# main1.net
KiCad netlist of a schematic drawn in EAGLE
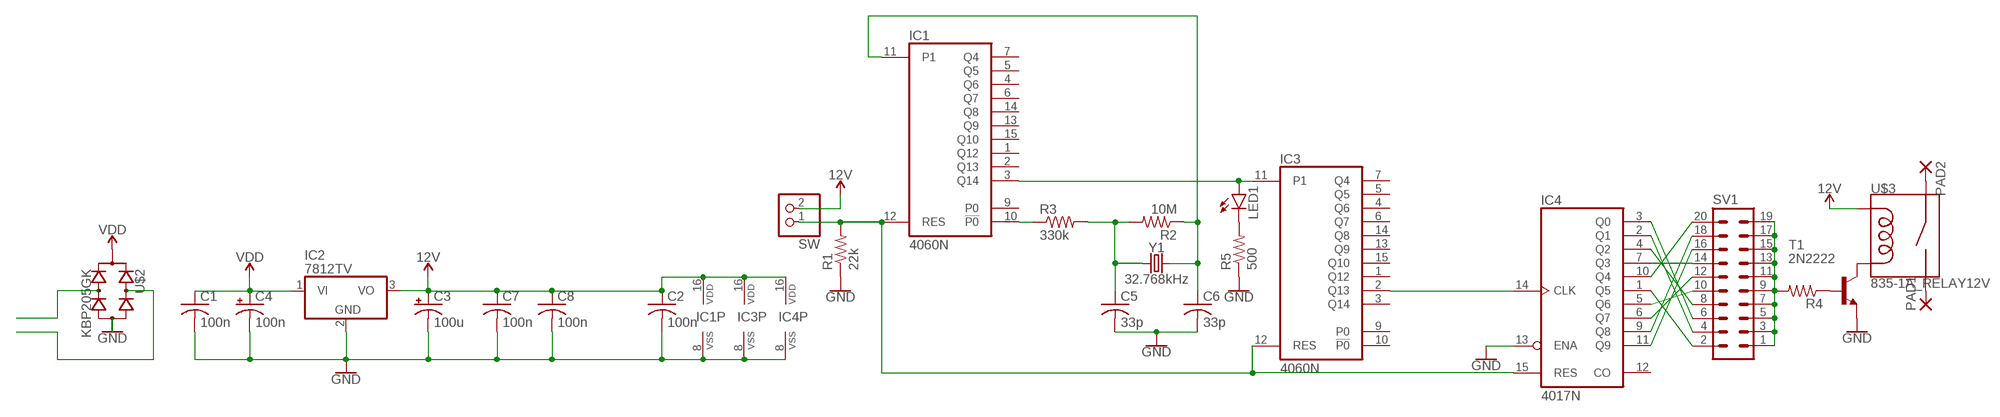
[diagram p0: schematic, sheet 1]

(export (version "E")
  (design (tool "Eeschema 10.0.6"))
  (components
    (comp (ref "C1")
      (value "100n")
      (footprint "eagle-import:C025-025X050")
      (libsource (lib "eagle-import") (part "C-US025-025X050"))
    )
    (comp (ref "C2")
      (value "100n")
      (footprint "eagle-import:C025-025X050")
      (libsource (lib "eagle-import") (part "C-US025-025X050"))
    )
    (comp (ref "C3")
      (value "100u")
      (footprint "eagle-import:E2-5")
      (libsource (lib "eagle-import") (part "CPOL-USE2-5"))
    )
    (comp (ref "C4")
      (value "100n")
      (footprint "eagle-import:E2-5")
      (libsource (lib "eagle-import") (part "CPOL-USE2-5"))
    )
    (comp (ref "C5")
      (value "33p")
      (footprint "eagle-import:C025-025X050")
      (libsource (lib "eagle-import") (part "C-US025-025X050"))
    )
    (comp (ref "C6")
      (value "33p")
      (footprint "eagle-import:C025-025X050")
      (libsource (lib "eagle-import") (part "C-US025-025X050"))
    )
    (comp (ref "C7")
      (value "100n")
      (footprint "eagle-import:C025-025X050")
      (libsource (lib "eagle-import") (part "C-US025-025X050"))
    )
    (comp (ref "C8")
      (value "100n")
      (footprint "eagle-import:C025-025X050")
      (libsource (lib "eagle-import") (part "C-US025-025X050"))
    )
    (comp (ref "IC1")
      (value "4060N")
      (footprint "eagle-import:DIL16")
      (libsource (lib "eagle-import") (part "4060N"))
    )
    (comp (ref "IC2")
      (value "7812TV")
      (footprint "eagle-import:TO220V")
      (libsource (lib "eagle-import") (part "78TV12"))
    )
    (comp (ref "IC3")
      (value "4060N")
      (footprint "eagle-import:DIL16")
      (libsource (lib "eagle-import") (part "4060N"))
    )
    (comp (ref "IC4")
      (value "4017N")
      (footprint "eagle-import:DIL16")
      (libsource (lib "eagle-import") (part "4017N"))
    )
    (comp (ref "LED1")
      (value "LED3MM")
      (footprint "eagle-import:LED3MM")
      (libsource (lib "eagle-import") (part "LED3MM"))
    )
    (comp (ref "PAD1")
      (value "2,54/1,0")
      (footprint "eagle-import:2,54_1,0")
      (libsource (lib "eagle-import") (part "2,54/1,0"))
    )
    (comp (ref "PAD2")
      (value "2,54/1,0")
      (footprint "eagle-import:2,54_1,0")
      (libsource (lib "eagle-import") (part "2,54/1,0"))
    )
    (comp (ref "R1")
      (value "22k")
      (footprint "eagle-import:0207_7")
      (libsource (lib "eagle-import") (part "R-US_0207/7"))
    )
    (comp (ref "R2")
      (value "10M")
      (footprint "eagle-import:0207_7")
      (libsource (lib "eagle-import") (part "R-US_0207/7"))
    )
    (comp (ref "R3")
      (value "330k")
      (footprint "eagle-import:0207_7")
      (libsource (lib "eagle-import") (part "R-US_0207/7"))
    )
    (comp (ref "R4")
      (value "R-US_0207/2V")
      (footprint "eagle-import:0207_2V")
      (libsource (lib "eagle-import") (part "R-US_0207/2V"))
    )
    (comp (ref "R5")
      (value "500")
      (footprint "eagle-import:0207_7")
      (libsource (lib "eagle-import") (part "R-US_0207/7"))
    )
    (comp (ref "SV1")
      (value "MA10-2")
      (footprint "eagle-import:MA10-2")
      (libsource (lib "eagle-import") (part "MA10-2"))
    )
    (comp (ref "SW")
      (value "PINHD-1X2")
      (footprint "eagle-import:1X02")
      (libsource (lib "eagle-import") (part "PINHD-1X2"))
    )
    (comp (ref "T1")
      (value "2N2222")
      (footprint "eagle-import:TO92-EBC-OVAL")
      (libsource (lib "eagle-import") (part "2N2222"))
    )
    (comp (ref "U$2")
      (value "KBP205GK")
      (footprint "eagle-import:KBP205G")
      (libsource (lib "eagle-import") (part "KBP205GK"))
    )
    (comp (ref "U$3")
      (value "835-1A_RELAY12V")
      (footprint "eagle-import:835-1A_RELAY_12V")
      (libsource (lib "eagle-import") (part "835-1A_RELAY12V"))
    )
    (comp (ref "Y1")
      (value "32.768kHz")
      (footprint "eagle-import:CRYSTAL-PTH-2X6-CYL")
      (libsource (lib "eagle-import") (part "CRYSTAL-32.768KHZPTH-2X6"))
    )
  )
  (nets
    (net (code "1") (name "12V") (class "Default")
      (node (ref "C2") (pin "1") (pinfunction "1_1") (pintype "passive"))
      (node (ref "C3") (pin "+") (pinfunction "+_+") (pintype "passive"))
      (node (ref "C7") (pin "1") (pinfunction "1_1") (pintype "passive"))
      (node (ref "C8") (pin "1") (pinfunction "1_1") (pintype "passive"))
      (node (ref "IC1") (pin "16") (pinfunction "VDD_16") (pintype "power_in"))
      (node (ref "IC2") (pin "3") (pinfunction "VO_3") (pintype "passive"))
      (node (ref "IC3") (pin "16") (pinfunction "VDD_16") (pintype "power_in"))
      (node (ref "IC4") (pin "16") (pinfunction "VDD_16") (pintype "power_in"))
      (node (ref "SW") (pin "2") (pinfunction "2_2") (pintype "passive"))
      (node (ref "U$3") (pin "P$1") (pinfunction "COIL1_P$1") (pintype "bidirectional"))
    )
    (net (code "2") (name "GND") (class "Default")
      (node (ref "C1") (pin "2") (pinfunction "2_2") (pintype "passive"))
      (node (ref "C2") (pin "2") (pinfunction "2_2") (pintype "passive"))
      (node (ref "C3") (pin "-") (pinfunction "-_-") (pintype "passive"))
      (node (ref "C4") (pin "-") (pinfunction "-_-") (pintype "passive"))
      (node (ref "C5") (pin "2") (pinfunction "2_2") (pintype "passive"))
      (node (ref "C6") (pin "2") (pinfunction "2_2") (pintype "passive"))
      (node (ref "C7") (pin "2") (pinfunction "2_2") (pintype "passive"))
      (node (ref "C8") (pin "2") (pinfunction "2_2") (pintype "passive"))
      (node (ref "IC1") (pin "8") (pinfunction "VSS_8") (pintype "power_in"))
      (node (ref "IC2") (pin "2") (pinfunction "GND_2") (pintype "passive"))
      (node (ref "IC3") (pin "8") (pinfunction "VSS_8") (pintype "power_in"))
      (node (ref "IC4") (pin "13") (pinfunction "ENA_13") (pintype "input"))
      (node (ref "IC4") (pin "8") (pinfunction "VSS_8") (pintype "power_in"))
      (node (ref "R1") (pin "1") (pinfunction "1_1") (pintype "passive"))
      (node (ref "R5") (pin "1") (pinfunction "1_1") (pintype "passive"))
      (node (ref "T1") (pin "E") (pinfunction "E_E") (pintype "passive"))
      (node (ref "U$2") (pin "-") (pinfunction "-_-") (pintype "passive"))
    )
    (net (code "3") (name "Net-(C5-Pad1)") (class "Default")
      (node (ref "C5") (pin "1") (pinfunction "1_1") (pintype "passive"))
      (node (ref "R2") (pin "2") (pinfunction "2_2") (pintype "passive"))
      (node (ref "R3") (pin "2") (pinfunction "2_2") (pintype "passive"))
      (node (ref "Y1") (pin "1") (pinfunction "1_1") (pintype "passive"))
    )
    (net (code "4") (name "Net-(IC1A-P1)") (class "Default")
      (node (ref "C6") (pin "1") (pinfunction "1_1") (pintype "passive"))
      (node (ref "IC1") (pin "11") (pinfunction "P1_11") (pintype "input"))
      (node (ref "R2") (pin "1") (pinfunction "1_1") (pintype "passive"))
      (node (ref "Y1") (pin "2") (pinfunction "2_2") (pintype "passive"))
    )
    (net (code "5") (name "Net-(IC1A-Q14)") (class "Default")
      (node (ref "IC1") (pin "3") (pinfunction "Q14_3") (pintype "output"))
      (node (ref "IC3") (pin "11") (pinfunction "P1_11") (pintype "input"))
      (node (ref "LED1") (pin "A") (pinfunction "A_A") (pintype "passive"))
    )
    (net (code "6") (name "Net-(IC1A-RES)") (class "Default")
      (node (ref "IC1") (pin "12") (pinfunction "RES_12") (pintype "input"))
      (node (ref "IC3") (pin "12") (pinfunction "RES_12") (pintype "input"))
      (node (ref "IC4") (pin "15") (pinfunction "RES_15") (pintype "input"))
      (node (ref "R1") (pin "2") (pinfunction "2_2") (pintype "passive"))
      (node (ref "SW") (pin "1") (pinfunction "1_1") (pintype "passive"))
    )
    (net (code "7") (name "Net-(IC1A-~{P0})") (class "Default")
      (node (ref "IC1") (pin "10") (pinfunction "~{P0}_10") (pintype "output"))
      (node (ref "R3") (pin "1") (pinfunction "1_1") (pintype "passive"))
    )
    (net (code "8") (name "Net-(IC3A-Q13)") (class "Default")
      (node (ref "IC3") (pin "2") (pinfunction "Q13_2") (pintype "output"))
      (node (ref "IC4") (pin "14") (pinfunction "CLK_14") (pintype "input"))
    )
    (net (code "9") (name "Net-(IC4A-Q0)") (class "Default")
      (node (ref "IC4") (pin "3") (pinfunction "Q0_3") (pintype "output"))
      (node (ref "SV1") (pin "6") (pinfunction "6_6") (pintype "passive"))
    )
    (net (code "10") (name "Net-(IC4A-Q1)") (class "Default")
      (node (ref "IC4") (pin "2") (pinfunction "Q1_2") (pintype "output"))
      (node (ref "SV1") (pin "4") (pinfunction "4_4") (pintype "passive"))
    )
    (net (code "11") (name "Net-(IC4A-Q2)") (class "Default")
      (node (ref "IC4") (pin "4") (pinfunction "Q2_4") (pintype "output"))
      (node (ref "SV1") (pin "8") (pinfunction "8_8") (pintype "passive"))
    )
    (net (code "12") (name "Net-(IC4A-Q3)") (class "Default")
      (node (ref "IC4") (pin "7") (pinfunction "Q3_7") (pintype "output"))
      (node (ref "SV1") (pin "14") (pinfunction "14_14") (pintype "passive"))
    )
    (net (code "13") (name "Net-(IC4A-Q4)") (class "Default")
      (node (ref "IC4") (pin "10") (pinfunction "Q4_10") (pintype "output"))
      (node (ref "SV1") (pin "20") (pinfunction "20_20") (pintype "passive"))
    )
    (net (code "14") (name "Net-(IC4A-Q5)") (class "Default")
      (node (ref "IC4") (pin "1") (pinfunction "Q5_1") (pintype "output"))
      (node (ref "SV1") (pin "2") (pinfunction "2_2") (pintype "passive"))
    )
    (net (code "15") (name "Net-(IC4A-Q6)") (class "Default")
      (node (ref "IC4") (pin "5") (pinfunction "Q6_5") (pintype "output"))
      (node (ref "SV1") (pin "10") (pinfunction "10_10") (pintype "passive"))
    )
    (net (code "16") (name "Net-(IC4A-Q7)") (class "Default")
      (node (ref "IC4") (pin "6") (pinfunction "Q7_6") (pintype "output"))
      (node (ref "SV1") (pin "12") (pinfunction "12_12") (pintype "passive"))
    )
    (net (code "17") (name "Net-(IC4A-Q8)") (class "Default")
      (node (ref "IC4") (pin "9") (pinfunction "Q8_9") (pintype "output"))
      (node (ref "SV1") (pin "18") (pinfunction "18_18") (pintype "passive"))
    )
    (net (code "18") (name "Net-(IC4A-Q9)") (class "Default")
      (node (ref "IC4") (pin "11") (pinfunction "Q9_11") (pintype "output"))
      (node (ref "SV1") (pin "16") (pinfunction "16_16") (pintype "passive"))
    )
    (net (code "19") (name "Net-(LED1-C)") (class "Default")
      (node (ref "LED1") (pin "K") (pinfunction "C_K") (pintype "passive"))
      (node (ref "R5") (pin "2") (pinfunction "2_2") (pintype "passive"))
    )
    (net (code "20") (name "Net-(PAD1-P)") (class "Default")
      (node (ref "PAD1") (pin "1") (pinfunction "P_1") (pintype "passive"))
      (node (ref "U$3") (pin "P$4") (pinfunction "NO_P$4") (pintype "bidirectional"))
    )
    (net (code "21") (name "Net-(PAD2-P)") (class "Default")
      (node (ref "PAD2") (pin "1") (pinfunction "P_1") (pintype "passive"))
      (node (ref "U$3") (pin "P$3") (pinfunction "MAIN_P$3") (pintype "bidirectional"))
    )
    (net (code "22") (name "Net-(R4-Pad1)") (class "Default")
      (node (ref "R4") (pin "1") (pinfunction "1_1") (pintype "passive"))
      (node (ref "T1") (pin "B") (pinfunction "B_B") (pintype "passive"))
    )
    (net (code "23") (name "Net-(R4-Pad2)") (class "Default")
      (node (ref "R4") (pin "2") (pinfunction "2_2") (pintype "passive"))
      (node (ref "SV1") (pin "1") (pinfunction "1_1") (pintype "passive"))
      (node (ref "SV1") (pin "11") (pinfunction "11_11") (pintype "passive"))
      (node (ref "SV1") (pin "13") (pinfunction "13_13") (pintype "passive"))
      (node (ref "SV1") (pin "15") (pinfunction "15_15") (pintype "passive"))
      (node (ref "SV1") (pin "17") (pinfunction "17_17") (pintype "passive"))
      (node (ref "SV1") (pin "19") (pinfunction "19_19") (pintype "passive"))
      (node (ref "SV1") (pin "3") (pinfunction "3_3") (pintype "passive"))
      (node (ref "SV1") (pin "5") (pinfunction "5_5") (pintype "passive"))
      (node (ref "SV1") (pin "7") (pinfunction "7_7") (pintype "passive"))
      (node (ref "SV1") (pin "9") (pinfunction "9_9") (pintype "passive"))
    )
    (net (code "24") (name "Net-(U$3-COIL2)") (class "Default")
      (node (ref "T1") (pin "C") (pinfunction "C_C") (pintype "passive"))
      (node (ref "U$3") (pin "P$2") (pinfunction "COIL2_P$2") (pintype "bidirectional"))
    )
    (net (code "25") (name "VDD") (class "Default")
      (node (ref "C1") (pin "1") (pinfunction "1_1") (pintype "passive"))
      (node (ref "C4") (pin "+") (pinfunction "+_+") (pintype "passive"))
      (node (ref "IC2") (pin "1") (pinfunction "VI_1") (pintype "input"))
      (node (ref "U$2") (pin "+") (pinfunction "+_+") (pintype "passive"))
    )
    (net (code "26") (name "unconnected-(IC1A-P0-Pad9)") (class "Default")
      (node (ref "IC1") (pin "9") (pinfunction "P0_9") (pintype "output"))
    )
    (net (code "27") (name "unconnected-(IC1A-Q4-Pad7)") (class "Default")
      (node (ref "IC1") (pin "7") (pinfunction "Q4_7") (pintype "output"))
    )
    (net (code "28") (name "unconnected-(IC1A-Q5-Pad5)") (class "Default")
      (node (ref "IC1") (pin "5") (pinfunction "Q5_5") (pintype "output"))
    )
    (net (code "29") (name "unconnected-(IC1A-Q6-Pad4)") (class "Default")
      (node (ref "IC1") (pin "4") (pinfunction "Q6_4") (pintype "output"))
    )
    (net (code "30") (name "unconnected-(IC1A-Q7-Pad6)") (class "Default")
      (node (ref "IC1") (pin "6") (pinfunction "Q7_6") (pintype "output"))
    )
    (net (code "31") (name "unconnected-(IC1A-Q8-Pad14)") (class "Default")
      (node (ref "IC1") (pin "14") (pinfunction "Q8_14") (pintype "output"))
    )
    (net (code "32") (name "unconnected-(IC1A-Q9-Pad13)") (class "Default")
      (node (ref "IC1") (pin "13") (pinfunction "Q9_13") (pintype "output"))
    )
    (net (code "33") (name "unconnected-(IC1A-Q10-Pad15)") (class "Default")
      (node (ref "IC1") (pin "15") (pinfunction "Q10_15") (pintype "output"))
    )
    (net (code "34") (name "unconnected-(IC1A-Q12-Pad1)") (class "Default")
      (node (ref "IC1") (pin "1") (pinfunction "Q12_1") (pintype "output"))
    )
    (net (code "35") (name "unconnected-(IC1A-Q13-Pad2)") (class "Default")
      (node (ref "IC1") (pin "2") (pinfunction "Q13_2") (pintype "output"))
    )
    (net (code "36") (name "unconnected-(IC3A-P0-Pad9)") (class "Default")
      (node (ref "IC3") (pin "9") (pinfunction "P0_9") (pintype "output"))
    )
    (net (code "37") (name "unconnected-(IC3A-Q4-Pad7)") (class "Default")
      (node (ref "IC3") (pin "7") (pinfunction "Q4_7") (pintype "output"))
    )
    (net (code "38") (name "unconnected-(IC3A-Q5-Pad5)") (class "Default")
      (node (ref "IC3") (pin "5") (pinfunction "Q5_5") (pintype "output"))
    )
    (net (code "39") (name "unconnected-(IC3A-Q6-Pad4)") (class "Default")
      (node (ref "IC3") (pin "4") (pinfunction "Q6_4") (pintype "output"))
    )
    (net (code "40") (name "unconnected-(IC3A-Q7-Pad6)") (class "Default")
      (node (ref "IC3") (pin "6") (pinfunction "Q7_6") (pintype "output"))
    )
    (net (code "41") (name "unconnected-(IC3A-Q8-Pad14)") (class "Default")
      (node (ref "IC3") (pin "14") (pinfunction "Q8_14") (pintype "output"))
    )
    (net (code "42") (name "unconnected-(IC3A-Q9-Pad13)") (class "Default")
      (node (ref "IC3") (pin "13") (pinfunction "Q9_13") (pintype "output"))
    )
    (net (code "43") (name "unconnected-(IC3A-Q10-Pad15)") (class "Default")
      (node (ref "IC3") (pin "15") (pinfunction "Q10_15") (pintype "output"))
    )
    (net (code "44") (name "unconnected-(IC3A-Q12-Pad1)") (class "Default")
      (node (ref "IC3") (pin "1") (pinfunction "Q12_1") (pintype "output"))
    )
    (net (code "45") (name "unconnected-(IC3A-Q14-Pad3)") (class "Default")
      (node (ref "IC3") (pin "3") (pinfunction "Q14_3") (pintype "output"))
    )
    (net (code "46") (name "unconnected-(IC3A-~{P0}-Pad10)") (class "Default")
      (node (ref "IC3") (pin "10") (pinfunction "~{P0}_10") (pintype "output"))
    )
    (net (code "47") (name "unconnected-(IC4A-CO-Pad12)") (class "Default")
      (node (ref "IC4") (pin "12") (pinfunction "CO_12") (pintype "output"))
    )
    (net (code "48") (name "unconnected-(U$2-AC-PadAC@1)") (class "Default")
      (node (ref "U$2") (pin "AC@1") (pinfunction "AC_AC@1") (pintype "passive"))
    )
    (net (code "49") (name "unconnected-(U$2-AC-PadAC@2)") (class "Default")
      (node (ref "U$2") (pin "AC@2") (pinfunction "AC_AC@2") (pintype "passive"))
    )
  )
)
